# 01-Power.net
KiCad netlist of a schematic drawn in Altium Designer
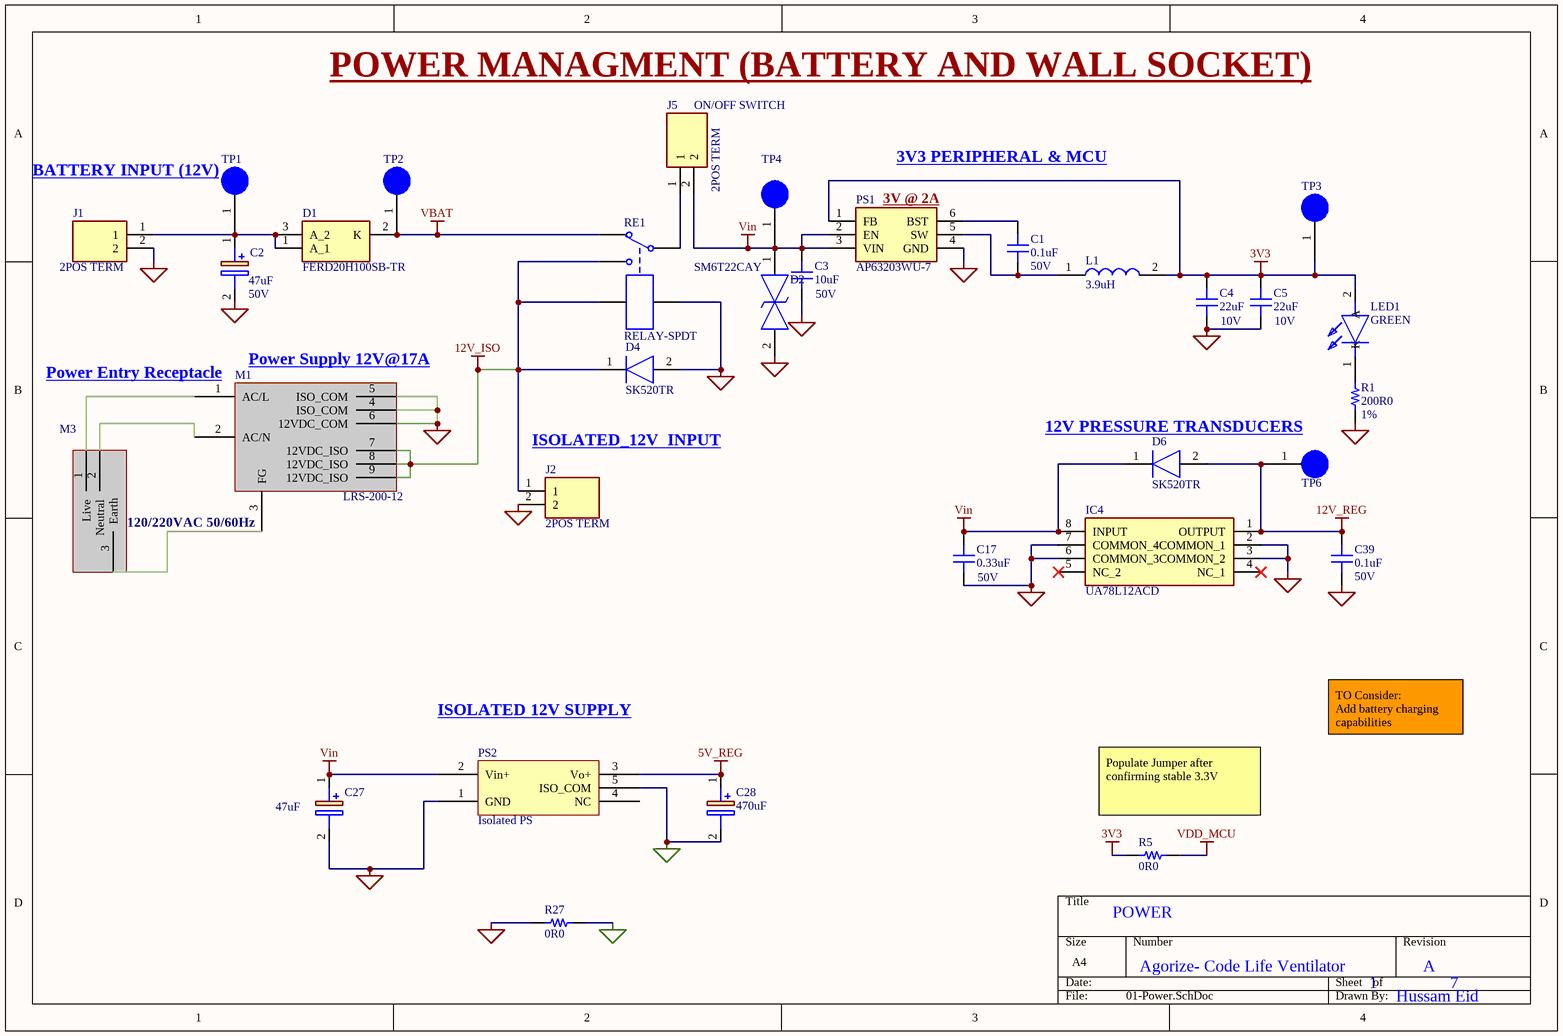
[diagram p0: 01-Power.SchDoc]

(export (version "E")
  (design (tool "Eeschema 10.0.6"))
  (components
    (comp (ref "C1")
      (value "0.1uF")
      (footprint "CAP 0603/1608")
      (description "CAP CER 0.1UF 50V X7R 0603")
      (fields (field (name "TOLERANCE") "20%") (field (name "VOLTAGE RATING") "50V"))
      (libsource (lib "Celestial Library Database") (part "Capacitor"))
    )
    (comp (ref "C2")
      (value "47uF")
      (footprint "SamacSys:EEE1HA470XP")
      (description "CAP ALUM 47UF 20% 50V SMD")
      (fields
        (field (name "TOLERANCE") "20%")
        (field (name "VOLTAGE RATING") "50V")
        (field (name "VOLTAGE") "50V")
      )
      (libsource (lib "*") (part "EEE-1HA470XP"))
    )
    (comp (ref "C3")
      (value "10uF")
      (footprint "CAP 1206/3216")
      (description "CAP CER 10UF 25V X7R 1206")
      (fields (field (name "TOLERANCE") "20%") (field (name "VOLTAGE RATING") "50V"))
      (libsource (lib "Celestial Library Database") (part "Capacitor"))
    )
    (comp (ref "C4")
      (value "22uF")
      (footprint "RES 0805/2012")
      (description "CAP CER 22UF 10V X5R 0805")
      (fields (field (name "VOLTAGE") "10V") (field (name "TOLERANCE") "20%"))
      (libsource (lib "Celestial Library Database") (part "Capacitor"))
    )
    (comp (ref "C5")
      (value "22uF")
      (footprint "RES 0805/2012")
      (description "CAP CER 22UF 10V X5R 0805")
      (fields (field (name "VOLTAGE") "10V") (field (name "TOLERANCE") "20%"))
      (libsource (lib "Celestial Library Database") (part "Capacitor"))
    )
    (comp (ref "C17")
      (value "0.33uF")
      (footprint "CAP 0603/1608")
      (description "CAP CER 0.33UF 50V X5R 0603")
      (fields (field (name "VOLTAGE RATING") "50V") (field (name "TOLERANCE") "10%"))
      (libsource (lib "Celestial Library Database") (part "Capacitor"))
    )
    (comp (ref "C27")
      (value "47uF")
      (footprint "SamacSys:CAPAE630X580N")
      (description "47uF ±20% 35V SMD,6.3x5.4mm Aluminum Electrolytic Capacitors")
      (libsource (lib "*") (part "CK0J221M-CRE54"))
    )
    (comp (ref "C28")
      (value "470uF")
      (footprint "SamacSys:CAPAE830X1050N")
      (description "Capacitor Polarised 470uF Alum")
      (libsource (lib "*") (part "25TRV220M8X10.5"))
    )
    (comp (ref "C39")
      (value "0.1uF")
      (footprint "CAP 0603/1608")
      (description "CAP CER 0.1UF 50V X7R 0603")
      (fields (field (name "TOLERANCE") "20%") (field (name "VOLTAGE RATING") "50V"))
      (libsource (lib "Celestial Library Database") (part "Capacitor"))
    )
    (comp (ref "D1")
      (value "FERD20H100SB-TR")
      (footprint "SamacSys:FERD20H100SBTR")
      (description "Diode")
      (fields
        (field (name "MOUSER PART NUMBER") "511-FERD20H100SB-TR")
        (field (name "RS PART NUMBER") "1241117P")
      )
      (libsource (lib "*") (part "FERD20H100SB-TR"))
    )
    (comp (ref "D2")
      (value "SM6T22CAY")
      (footprint "SamacSys:DIONM5436X265N")
      (description "TVS Diode (Bi-directional)")
      (fields (field (name "MOUSER PART NUMBER") "511-SM6T22CAY") (field (name "RS PART NUMBER") "7957219P"))
      (libsource (lib "*") (part "SM6T22CAY"))
    )
    (comp (ref "D4")
      (value "SK520TR")
      (footprint "SamacSys:DIOM8060X295N")
      (description "DIODE SCHOTTKY 200V 5A SMC")
      (libsource (lib "*") (part "SK520TR"))
    )
    (comp (ref "D6")
      (value "SK520TR")
      (footprint "SamacSys:DIOM8060X295N")
      (description "DIODE SCHOTTKY 200V 5A SMC")
      (libsource (lib "*") (part "SK520TR"))
    )
    (comp (ref "IC4")
      (value "UA78L12ACD")
      (footprint "SamacSys:SOIC127P600X175-8N")
      (description "Linear Voltage Regulator IC  1 Output  100mA 8-SOIC")
      (fields (field (name "MOUSER PART NUMBER") "595-UA78L12ACD") (field (name "RS PART NUMBER") "6616727P"))
      (libsource (lib "*") (part "UA78L12ACD"))
    )
    (comp (ref "J1")
      (value "2POS TERM")
      (footprint "PcbLib1:SHDR2W110P0X500_1X2_1000X830X1140P")
      (description "TERM BLK 2POS SIDE ENTRY 5MM PCB")
      (fields (field (name "VOLTAGE") "300V"))
      (libsource (lib "") (part "1935161_1"))
    )
    (comp (ref "J2")
      (value "2POS TERM")
      (footprint "PcbLib1:SHDR2W110P0X500_1X2_1000X830X1140P")
      (description "TERM BLK 2POS SIDE ENTRY 5MM PCB")
      (fields (field (name "VOLTAGE") "300V"))
      (libsource (lib "*") (part "1935161"))
    )
    (comp (ref "J5")
      (value "2POS TERM")
      (footprint "PcbLib1:SHDR2W110P0X500_1X2_1000X830X1140P")
      (description "TERM BLK 2POS SIDE ENTRY 5MM PCB")
      (fields (field (name "VOLTAGE") "300V"))
      (libsource (lib "") (part "1935161_2"))
    )
    (comp (ref "L1")
      (value "3.9uH")
      (footprint "SamacSys:1255AY100MP3")
      (description "3.9µH Shielded Wirewound Inductor 4.2A 26.4mOhm Max Nonstandard")
      (fields (field (name "TOLERANCE") "30%"))
      (libsource (lib "*") (part "1255AY-3R9N=P3"))
    )
    (comp (ref "LED1")
      (value "GREEN")
      (footprint "SamacSys:150060GS73220")
      (description "LED GREEN CLEAR 0603 SMD")
      (libsource (lib "*") (part "150060GS73220"))
    )
    (comp (ref "M1")
      (value "12V 204W PS")
      (description "Enclosed AC DC Converters 1 Output 12V    17A 90 ~ 132 VAC, 180 ~ 264 VAC, 240 ~ 370 VDC Input")
      (fields (field (name "MANUFACTURER PART NUMBER 1") "LRS-200-12"))
      (libsource (lib "Schlib1") (part "12V 204W PS"))
    )
    (comp (ref "M3")
      (value "Power Entry Receptacle")
      (description "Power Entry Connector Receptacle, Male Blades IEC 320-C14 Panel Mount, Flange")
      (libsource (lib "Schlib1") (part "Power Entry Receptacle"))
    )
    (comp (ref "PS1")
      (value "AP63203WU-7")
      (footprint "SamacSys:SOT95P280X100-6N")
      (description "IC REG BUCK 3.3V 2A TSOT26")
      (libsource (lib "*") (part "AP63203WU-7"))
    )
    (comp (ref "PS2")
      (value "Isolated PS")
      (footprint "ISO_PS")
      (description "5V 1.2A Though Hole Power Modules")
      (libsource (lib "Schlib1") (part "Isolated PS"))
    )
    (comp (ref "R1")
      (value "200R0")
      (footprint "RES 1206/3216")
      (description "RES SMD 10K OHM 1% 1/4W 1206")
      (fields (field (name "TOLERANCE") "1%"))
      (libsource (lib "Celestial Library Database") (part "Resistor"))
    )
    (comp (ref "R5")
      (value "0R0")
      (footprint "RES 0603/1608")
      (description "RES SMD 0 OHM JUMPER 1/10W 0603")
      (fields (field (name "TOLERANCE") "0%"))
      (libsource (lib "Celestial Library Database") (part "Resistor"))
    )
    (comp (ref "R27")
      (value "0R0")
      (footprint "RES 0603/1608")
      (description "RES SMD 0 OHM JUMPER 1/10W 0603")
      (fields (field (name "TOLERANCE") "0%"))
      (libsource (lib "Celestial Library Database") (part "Resistor"))
    )
    (comp (ref "RE1")
      (value "RELAY-SPDT")
      (footprint "T9GV5L145")
      (description "RELAY GEN PURPOSE SPDT 20A 12V")
      (libsource (lib "Schlib1") (part "RELAY-SPDT"))
    )
    (comp (ref "TP1")
      (value "TP")
      (footprint "TP")
      (description "Test Point")
      (libsource (lib "Schlib1") (part "TP"))
    )
    (comp (ref "TP2")
      (value "TP")
      (footprint "TP")
      (description "Test Point")
      (libsource (lib "Schlib1") (part "TP"))
    )
    (comp (ref "TP3")
      (value "TP")
      (footprint "TP")
      (description "Test Point")
      (libsource (lib "Schlib1") (part "TP"))
    )
    (comp (ref "TP4")
      (value "TP")
      (footprint "TP")
      (description "Test Point")
      (libsource (lib "Schlib1") (part "TP"))
    )
    (comp (ref "TP6")
      (value "TP")
      (footprint "TP")
      (description "Test Point")
      (libsource (lib "Schlib1") (part "TP"))
    )
  )
  (nets
    (net (code "1") (name "3V3") (class "Default")
      (node (ref "C4") (pin "2") (pinfunction "2_2") (pintype "passive"))
      (node (ref "C5") (pin "2") (pinfunction "2_2") (pintype "passive"))
      (node (ref "L1") (pin "2") (pinfunction "2_2") (pintype "passive"))
      (node (ref "LED1") (pin "2") (pinfunction "A_2") (pintype "passive"))
      (node (ref "PS1") (pin "1") (pinfunction "FB_1") (pintype "passive"))
      (node (ref "R5") (pin "1") (pinfunction "1_1") (pintype "passive"))
      (node (ref "TP3") (pin "1") (pinfunction "1_1") (pintype "passive"))
    )
    (net (code "2") (name "5V_REG") (class "Default")
      (node (ref "C28") (pin "1") (pinfunction "+_1") (pintype "passive"))
      (node (ref "PS2") (pin "3") (pinfunction "Vo+_3") (pintype "passive"))
    )
    (net (code "3") (name "12V_ISO") (class "Default")
      (node (ref "D4") (pin "1") (pinfunction "K_1") (pintype "passive"))
      (node (ref "J2") (pin "1") (pinfunction "1_1") (pintype "passive"))
      (node (ref "M1") (pin "7") (pinfunction "12VDC_ISO_7") (pintype "passive"))
      (node (ref "M1") (pin "8") (pinfunction "12VDC_ISO_8") (pintype "passive"))
      (node (ref "M1") (pin "9") (pinfunction "12VDC_ISO_9") (pintype "passive"))
      (node (ref "RE1") (pin "3") (pinfunction "3_3") (pintype "passive"))
      (node (ref "RE1") (pin "4") (pinfunction "4_4") (pintype "passive"))
    )
    (net (code "4") (name "12V_REG") (class "Default")
      (node (ref "C39") (pin "1") (pinfunction "1_1") (pintype "passive"))
      (node (ref "D6") (pin "2") (pinfunction "A_2") (pintype "passive"))
      (node (ref "IC4") (pin "1") (pinfunction "OUTPUT_1") (pintype "passive"))
      (node (ref "TP6") (pin "1") (pinfunction "1_1") (pintype "passive"))
    )
    (net (code "5") (name "COM") (class "Default")
      (node (ref "C17") (pin "2") (pinfunction "2_2") (pintype "passive"))
      (node (ref "C2") (pin "2") (pinfunction "-_2") (pintype "passive"))
      (node (ref "C27") (pin "2") (pinfunction "-_2") (pintype "passive"))
      (node (ref "C3") (pin "1") (pinfunction "1_1") (pintype "passive"))
      (node (ref "C39") (pin "2") (pinfunction "2_2") (pintype "passive"))
      (node (ref "C4") (pin "1") (pinfunction "1_1") (pintype "passive"))
      (node (ref "C5") (pin "1") (pinfunction "1_1") (pintype "passive"))
      (node (ref "D2") (pin "2") (pinfunction "2_2") (pintype "passive"))
      (node (ref "D4") (pin "2") (pinfunction "A_2") (pintype "passive"))
      (node (ref "IC4") (pin "2") (pinfunction "COMMON_1_2") (pintype "passive"))
      (node (ref "IC4") (pin "3") (pinfunction "COMMON_2_3") (pintype "passive"))
      (node (ref "IC4") (pin "6") (pinfunction "COMMON_3_6") (pintype "passive"))
      (node (ref "IC4") (pin "7") (pinfunction "COMMON_4_7") (pintype "passive"))
      (node (ref "J1") (pin "2") (pinfunction "2_2") (pintype "passive"))
      (node (ref "J2") (pin "2") (pinfunction "2_2") (pintype "passive"))
      (node (ref "M1") (pin "4") (pinfunction "ISO_COM_4") (pintype "passive"))
      (node (ref "M1") (pin "5") (pinfunction "ISO_COM_5") (pintype "passive"))
      (node (ref "M1") (pin "6") (pinfunction "12VDC_COM_6") (pintype "passive"))
      (node (ref "PS1") (pin "4") (pinfunction "GND_4") (pintype "power_in"))
      (node (ref "PS2") (pin "1") (pinfunction "GND_1") (pintype "passive"))
      (node (ref "R1") (pin "1") (pinfunction "1_1") (pintype "passive"))
      (node (ref "R27") (pin "1") (pinfunction "1_1") (pintype "passive"))
      (node (ref "RE1") (pin "2") (pinfunction "2_2") (pintype "passive"))
    )
    (net (code "6") (name "COM_ISO") (class "Default")
      (node (ref "C28") (pin "2") (pinfunction "-_2") (pintype "passive"))
      (node (ref "PS2") (pin "5") (pinfunction "ISO_COM_5") (pintype "passive"))
      (node (ref "R27") (pin "2") (pinfunction "2_2") (pintype "passive"))
    )
    (net (code "7") (name "Net-(C2-+)") (class "Default")
      (node (ref "C2") (pin "1") (pinfunction "+_1") (pintype "passive"))
      (node (ref "D1") (pin "1") (pinfunction "A_1_1") (pintype "passive"))
      (node (ref "D1") (pin "3") (pinfunction "A_2_3") (pintype "passive"))
      (node (ref "J1") (pin "1") (pinfunction "1_1") (pintype "passive"))
      (node (ref "TP1") (pin "1") (pinfunction "1_1") (pintype "passive"))
    )
    (net (code "8") (name "Net-(J5-Pad1)") (class "Default")
      (node (ref "J5") (pin "1") (pinfunction "1_1") (pintype "passive"))
      (node (ref "RE1") (pin "1") (pinfunction "1_1") (pintype "passive"))
    )
    (net (code "9") (name "Net-(LED1-K)") (class "Default")
      (node (ref "LED1") (pin "1") (pinfunction "K_1") (pintype "passive"))
      (node (ref "R1") (pin "2") (pinfunction "2_2") (pintype "passive"))
    )
    (net (code "10") (name "Net-(M1-AC{slash}L)") (class "Default")
      (node (ref "M1") (pin "1") (pinfunction "AC/L_1") (pintype "passive"))
      (node (ref "M3") (pin "1") (pinfunction "Live_1") (pintype "passive"))
    )
    (net (code "11") (name "Net-(M1-AC{slash}N)") (class "Default")
      (node (ref "M1") (pin "2") (pinfunction "AC/N_2") (pintype "passive"))
      (node (ref "M3") (pin "2") (pinfunction "Neutral_2") (pintype "passive"))
    )
    (net (code "12") (name "Net-(M1-FG)") (class "Default")
      (node (ref "M1") (pin "3") (pinfunction "FG_3") (pintype "passive"))
      (node (ref "M3") (pin "3") (pinfunction "Earth_3") (pintype "passive"))
    )
    (net (code "13") (name "Net-(PS1-BST)") (class "Default")
      (node (ref "C1") (pin "1") (pinfunction "1_1") (pintype "passive"))
      (node (ref "PS1") (pin "6") (pinfunction "BST_6") (pintype "passive"))
    )
    (net (code "14") (name "Net-(PS1-SW)") (class "Default")
      (node (ref "C1") (pin "2") (pinfunction "2_2") (pintype "passive"))
      (node (ref "L1") (pin "1") (pinfunction "1_1") (pintype "passive"))
      (node (ref "PS1") (pin "5") (pinfunction "SW_5") (pintype "passive"))
    )
    (net (code "15") (name "VBAT") (class "Default")
      (node (ref "D1") (pin "2") (pinfunction "K_2") (pintype "passive"))
      (node (ref "RE1") (pin "5") (pinfunction "5_5") (pintype "passive"))
      (node (ref "TP2") (pin "1") (pinfunction "1_1") (pintype "passive"))
    )
    (net (code "16") (name "VDD_MCU") (class "Default")
      (node (ref "R5") (pin "2") (pinfunction "2_2") (pintype "passive"))
    )
    (net (code "17") (name "Vin") (class "Default")
      (node (ref "C17") (pin "1") (pinfunction "1_1") (pintype "passive"))
      (node (ref "C27") (pin "1") (pinfunction "+_1") (pintype "passive"))
      (node (ref "C3") (pin "2") (pinfunction "2_2") (pintype "passive"))
      (node (ref "D2") (pin "1") (pinfunction "1_1") (pintype "passive"))
      (node (ref "D6") (pin "1") (pinfunction "K_1") (pintype "passive"))
      (node (ref "IC4") (pin "8") (pinfunction "INPUT_8") (pintype "passive"))
      (node (ref "J5") (pin "2") (pinfunction "2_2") (pintype "passive"))
      (node (ref "PS1") (pin "2") (pinfunction "EN_2") (pintype "passive"))
      (node (ref "PS1") (pin "3") (pinfunction "VIN_3") (pintype "power_in"))
      (node (ref "PS2") (pin "2") (pinfunction "Vin+_2") (pintype "passive"))
      (node (ref "TP4") (pin "1") (pinfunction "1_1") (pintype "passive"))
    )
    (net (code "18") (name "unconnected-(IC4-NC_1-Pad4)") (class "Default")
      (node (ref "IC4") (pin "4") (pinfunction "NC_1_4") (pintype "passive+no_connect"))
    )
    (net (code "19") (name "unconnected-(IC4-NC_2-Pad5)") (class "Default")
      (node (ref "IC4") (pin "5") (pinfunction "NC_2_5") (pintype "passive+no_connect"))
    )
    (net (code "20") (name "unconnected-(PS2-NC-Pad4)") (class "Default")
      (node (ref "PS2") (pin "4") (pinfunction "NC_4") (pintype "passive"))
    )
  )
)
